# 201_GridPos2.net
KiCad netlist of a schematic drawn in Altium Designer
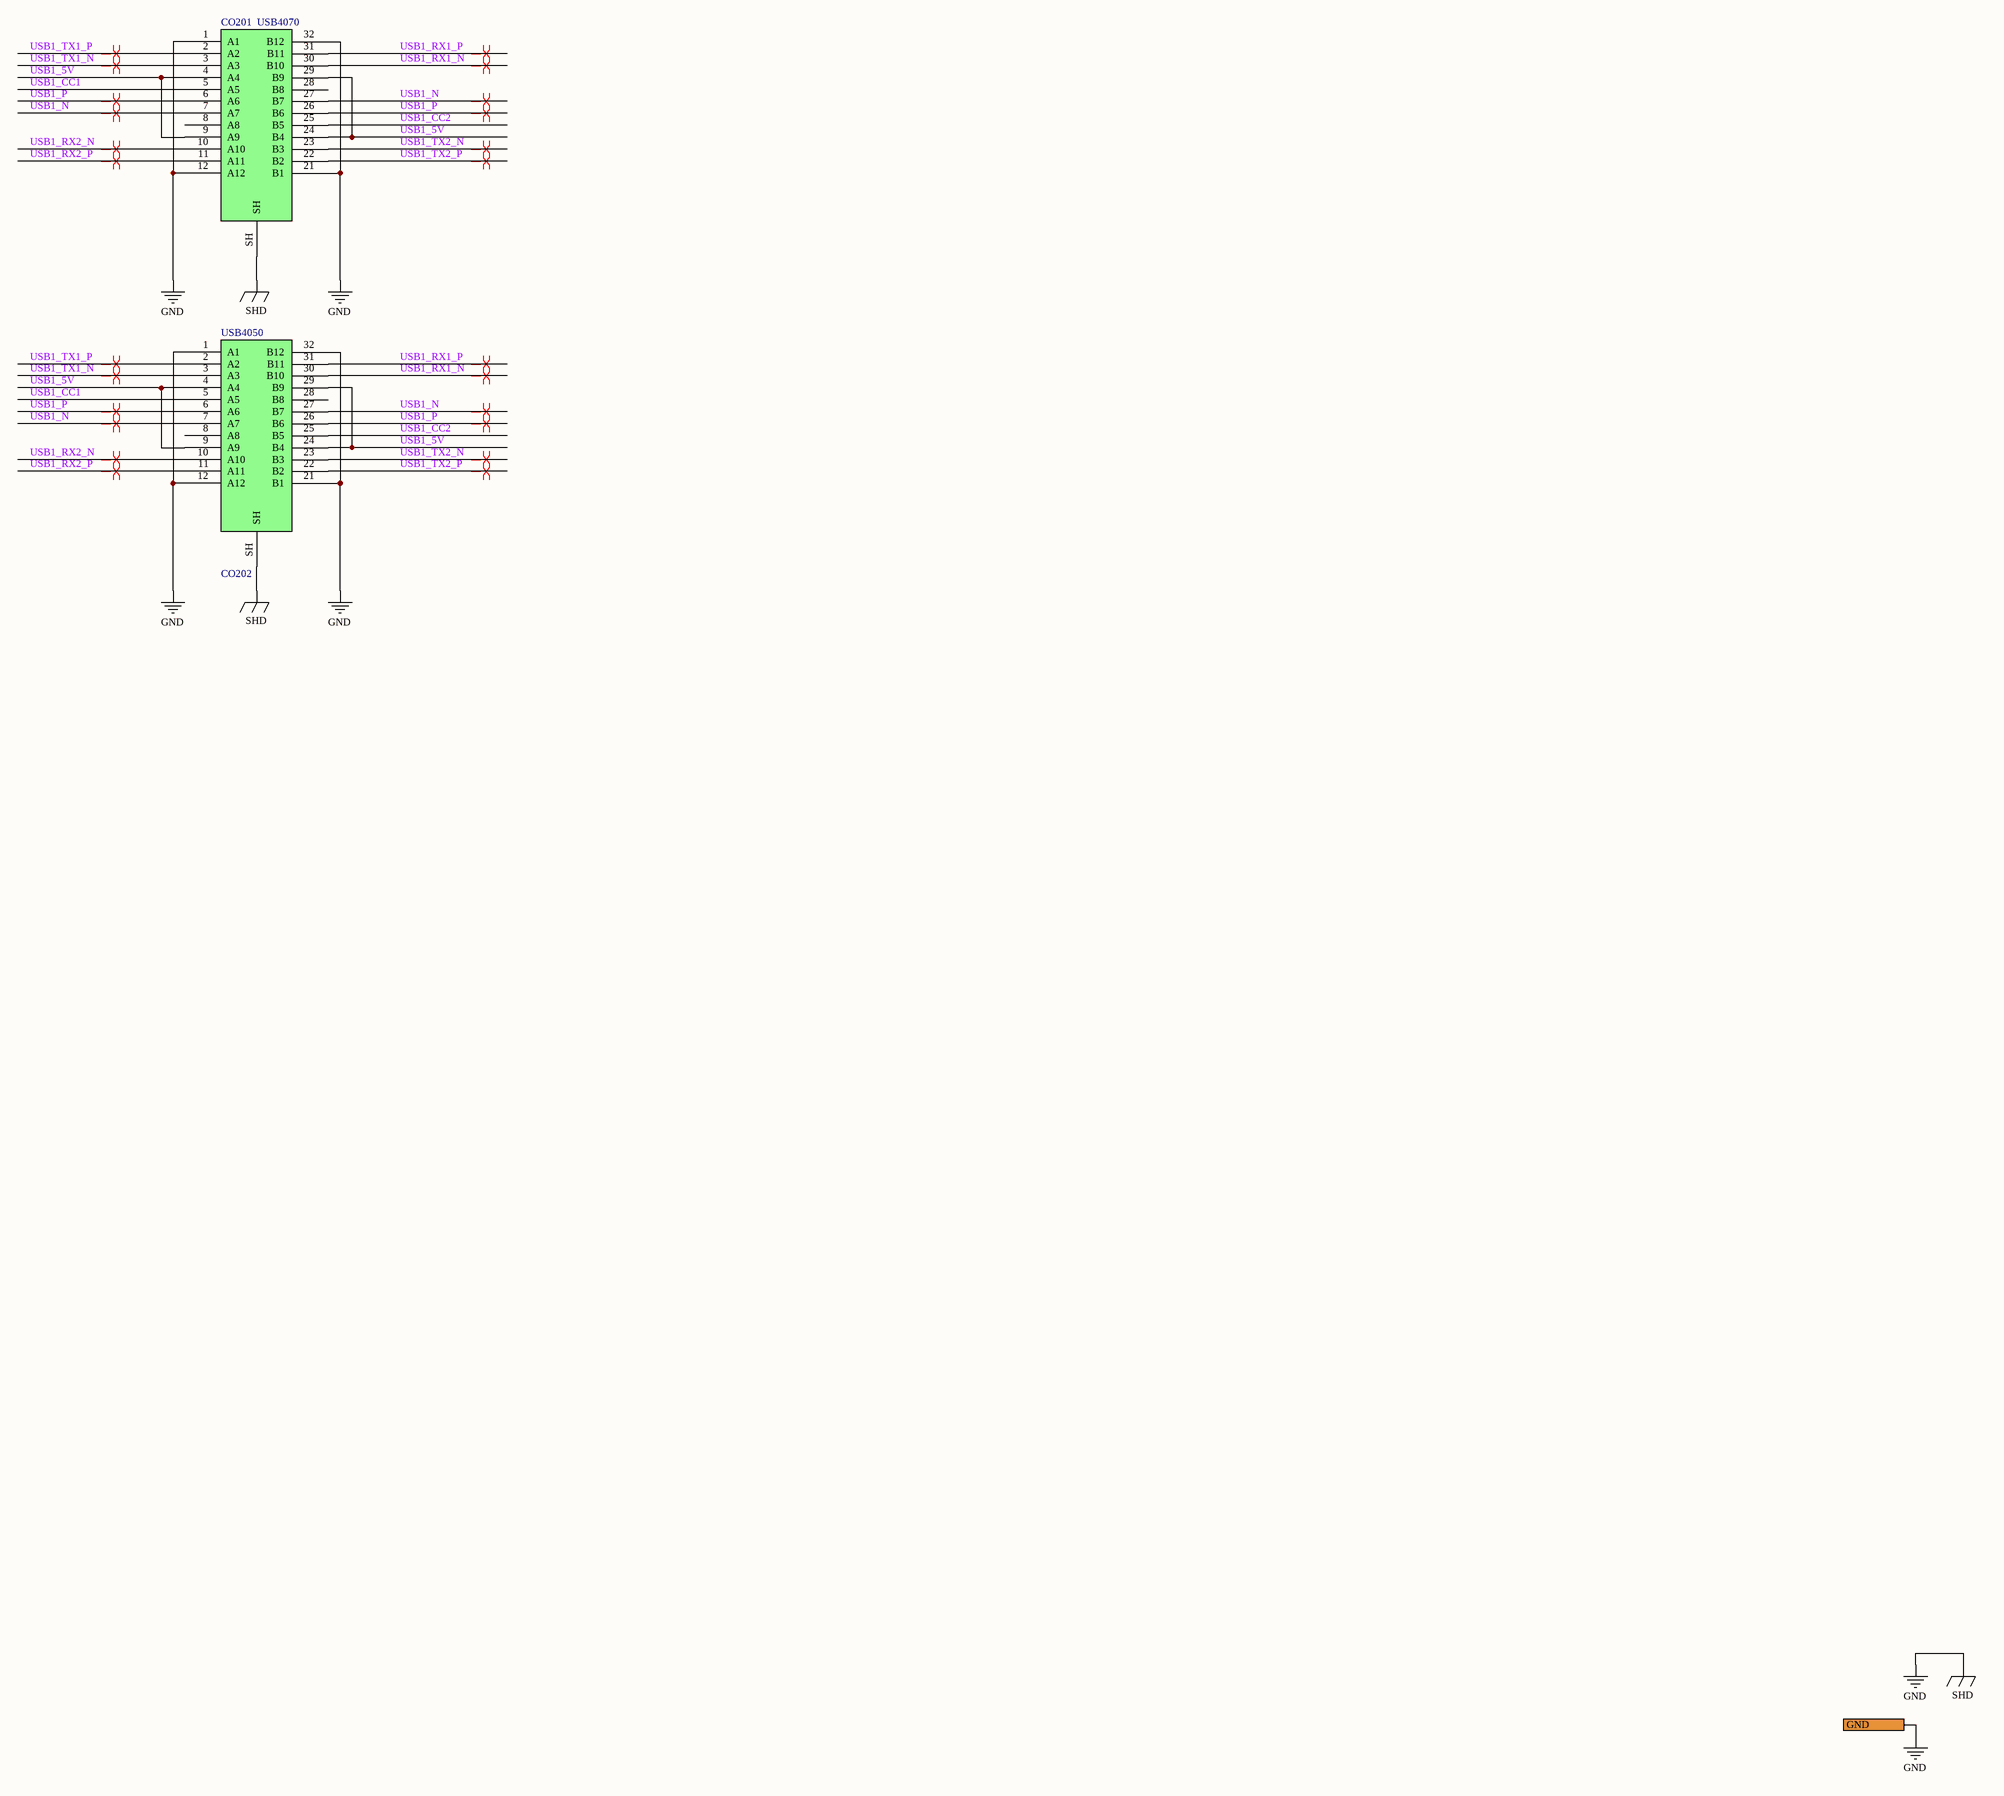
[diagram p0: 201_GridPos2.SchDoc]

(export (version "E")
  (design (tool "Eeschema 10.0.6"))
  (components
    (comp (ref "CO201")
      (value "USB4070")
      (footprint "USB4070-30-C")
      (description "USB4070-30-C")
      (fields (field (name "REFVAL") "USB4070") (field (name "PART NUMBER") "CO0021"))
      (libsource (lib "") (part "USB-CC_1"))
    )
    (comp (ref "CO202")
      (value "USB4050")
      (footprint "USB4050-30-A")
      (description "USB C connector Receptacle Horizontal")
      (fields
        (field (name "REFVAL") "USB4050")
        (field (name "PART NUMBER") "CO0039")
        (field (name "MANFACTPART") "USB4050-30-A")
      )
      (libsource (lib "GTS_Database") (part "USB-CC"))
    )
  )
  (nets
    (net (code "1") (name "/USB1_5V") (class "Default")
      (node (ref "CO201") (pin "24") (pinfunction "B4_24") (pintype "passive"))
      (node (ref "CO201") (pin "29") (pinfunction "B9_29") (pintype "passive"))
      (node (ref "CO201") (pin "4") (pinfunction "A4_4") (pintype "passive"))
      (node (ref "CO201") (pin "9") (pinfunction "A9_9") (pintype "passive"))
      (node (ref "CO202") (pin "24") (pinfunction "B4_24") (pintype "passive"))
      (node (ref "CO202") (pin "29") (pinfunction "B9_29") (pintype "passive"))
      (node (ref "CO202") (pin "4") (pinfunction "A4_4") (pintype "passive"))
      (node (ref "CO202") (pin "9") (pinfunction "A9_9") (pintype "passive"))
    )
    (net (code "2") (name "/USB1_CC1") (class "Default")
      (node (ref "CO201") (pin "5") (pinfunction "A5_5") (pintype "passive"))
      (node (ref "CO202") (pin "5") (pinfunction "A5_5") (pintype "passive"))
    )
    (net (code "3") (name "/USB1_CC2") (class "Default")
      (node (ref "CO201") (pin "25") (pinfunction "B5_25") (pintype "passive"))
      (node (ref "CO202") (pin "25") (pinfunction "B5_25") (pintype "passive"))
    )
    (net (code "4") (name "/USB1_N") (class "Default")
      (node (ref "CO201") (pin "27") (pinfunction "B7_27") (pintype "passive"))
      (node (ref "CO201") (pin "7") (pinfunction "A7_7") (pintype "passive"))
      (node (ref "CO202") (pin "27") (pinfunction "B7_27") (pintype "passive"))
      (node (ref "CO202") (pin "7") (pinfunction "A7_7") (pintype "passive"))
    )
    (net (code "5") (name "/USB1_P") (class "Default")
      (node (ref "CO201") (pin "26") (pinfunction "B6_26") (pintype "passive"))
      (node (ref "CO201") (pin "6") (pinfunction "A6_6") (pintype "passive"))
      (node (ref "CO202") (pin "26") (pinfunction "B6_26") (pintype "passive"))
      (node (ref "CO202") (pin "6") (pinfunction "A6_6") (pintype "passive"))
    )
    (net (code "6") (name "/USB1_RX1_N") (class "Default")
      (node (ref "CO201") (pin "30") (pinfunction "B10_30") (pintype "passive"))
      (node (ref "CO202") (pin "30") (pinfunction "B10_30") (pintype "passive"))
    )
    (net (code "7") (name "/USB1_RX1_P") (class "Default")
      (node (ref "CO201") (pin "31") (pinfunction "B11_31") (pintype "passive"))
      (node (ref "CO202") (pin "31") (pinfunction "B11_31") (pintype "passive"))
    )
    (net (code "8") (name "/USB1_RX2_N") (class "Default")
      (node (ref "CO201") (pin "10") (pinfunction "A10_10") (pintype "passive"))
      (node (ref "CO202") (pin "10") (pinfunction "A10_10") (pintype "passive"))
    )
    (net (code "9") (name "/USB1_RX2_P") (class "Default")
      (node (ref "CO201") (pin "11") (pinfunction "A11_11") (pintype "passive"))
      (node (ref "CO202") (pin "11") (pinfunction "A11_11") (pintype "passive"))
    )
    (net (code "10") (name "/USB1_TX1_N") (class "Default")
      (node (ref "CO201") (pin "3") (pinfunction "A3_3") (pintype "passive"))
      (node (ref "CO202") (pin "3") (pinfunction "A3_3") (pintype "passive"))
    )
    (net (code "11") (name "/USB1_TX1_P") (class "Default")
      (node (ref "CO201") (pin "2") (pinfunction "A2_2") (pintype "passive"))
      (node (ref "CO202") (pin "2") (pinfunction "A2_2") (pintype "passive"))
    )
    (net (code "12") (name "/USB1_TX2_N") (class "Default")
      (node (ref "CO201") (pin "23") (pinfunction "B3_23") (pintype "passive"))
      (node (ref "CO202") (pin "23") (pinfunction "B3_23") (pintype "passive"))
    )
    (net (code "13") (name "/USB1_TX2_P") (class "Default")
      (node (ref "CO201") (pin "22") (pinfunction "B2_22") (pintype "passive"))
      (node (ref "CO202") (pin "22") (pinfunction "B2_22") (pintype "passive"))
    )
    (net (code "14") (name "GND") (class "Default")
      (node (ref "CO201") (pin "1") (pinfunction "A1_1") (pintype "passive"))
      (node (ref "CO201") (pin "12") (pinfunction "A12_12") (pintype "passive"))
      (node (ref "CO201") (pin "21") (pinfunction "B1_21") (pintype "passive"))
      (node (ref "CO201") (pin "32") (pinfunction "B12_32") (pintype "passive"))
      (node (ref "CO201") (pin "SH") (pinfunction "SH_SH") (pintype "power_in"))
      (node (ref "CO202") (pin "1") (pinfunction "A1_1") (pintype "passive"))
      (node (ref "CO202") (pin "12") (pinfunction "A12_12") (pintype "passive"))
      (node (ref "CO202") (pin "21") (pinfunction "B1_21") (pintype "passive"))
      (node (ref "CO202") (pin "32") (pinfunction "B12_32") (pintype "passive"))
      (node (ref "CO202") (pin "SH") (pinfunction "SH_SH") (pintype "power_in"))
    )
    (net (code "15") (name "unconnected-(CO201-A8-Pad8)") (class "Default")
      (node (ref "CO201") (pin "8") (pinfunction "A8_8") (pintype "passive"))
    )
    (net (code "16") (name "unconnected-(CO201-B8-Pad28)") (class "Default")
      (node (ref "CO201") (pin "28") (pinfunction "B8_28") (pintype "passive"))
    )
    (net (code "17") (name "unconnected-(CO202-A8-Pad8)") (class "Default")
      (node (ref "CO202") (pin "8") (pinfunction "A8_8") (pintype "passive"))
    )
    (net (code "18") (name "unconnected-(CO202-B8-Pad28)") (class "Default")
      (node (ref "CO202") (pin "28") (pinfunction "B8_28") (pintype "passive"))
    )
  )
)
